# Quad_FC_V10_5.net
KiCad netlist of a schematic drawn in Altium Designer
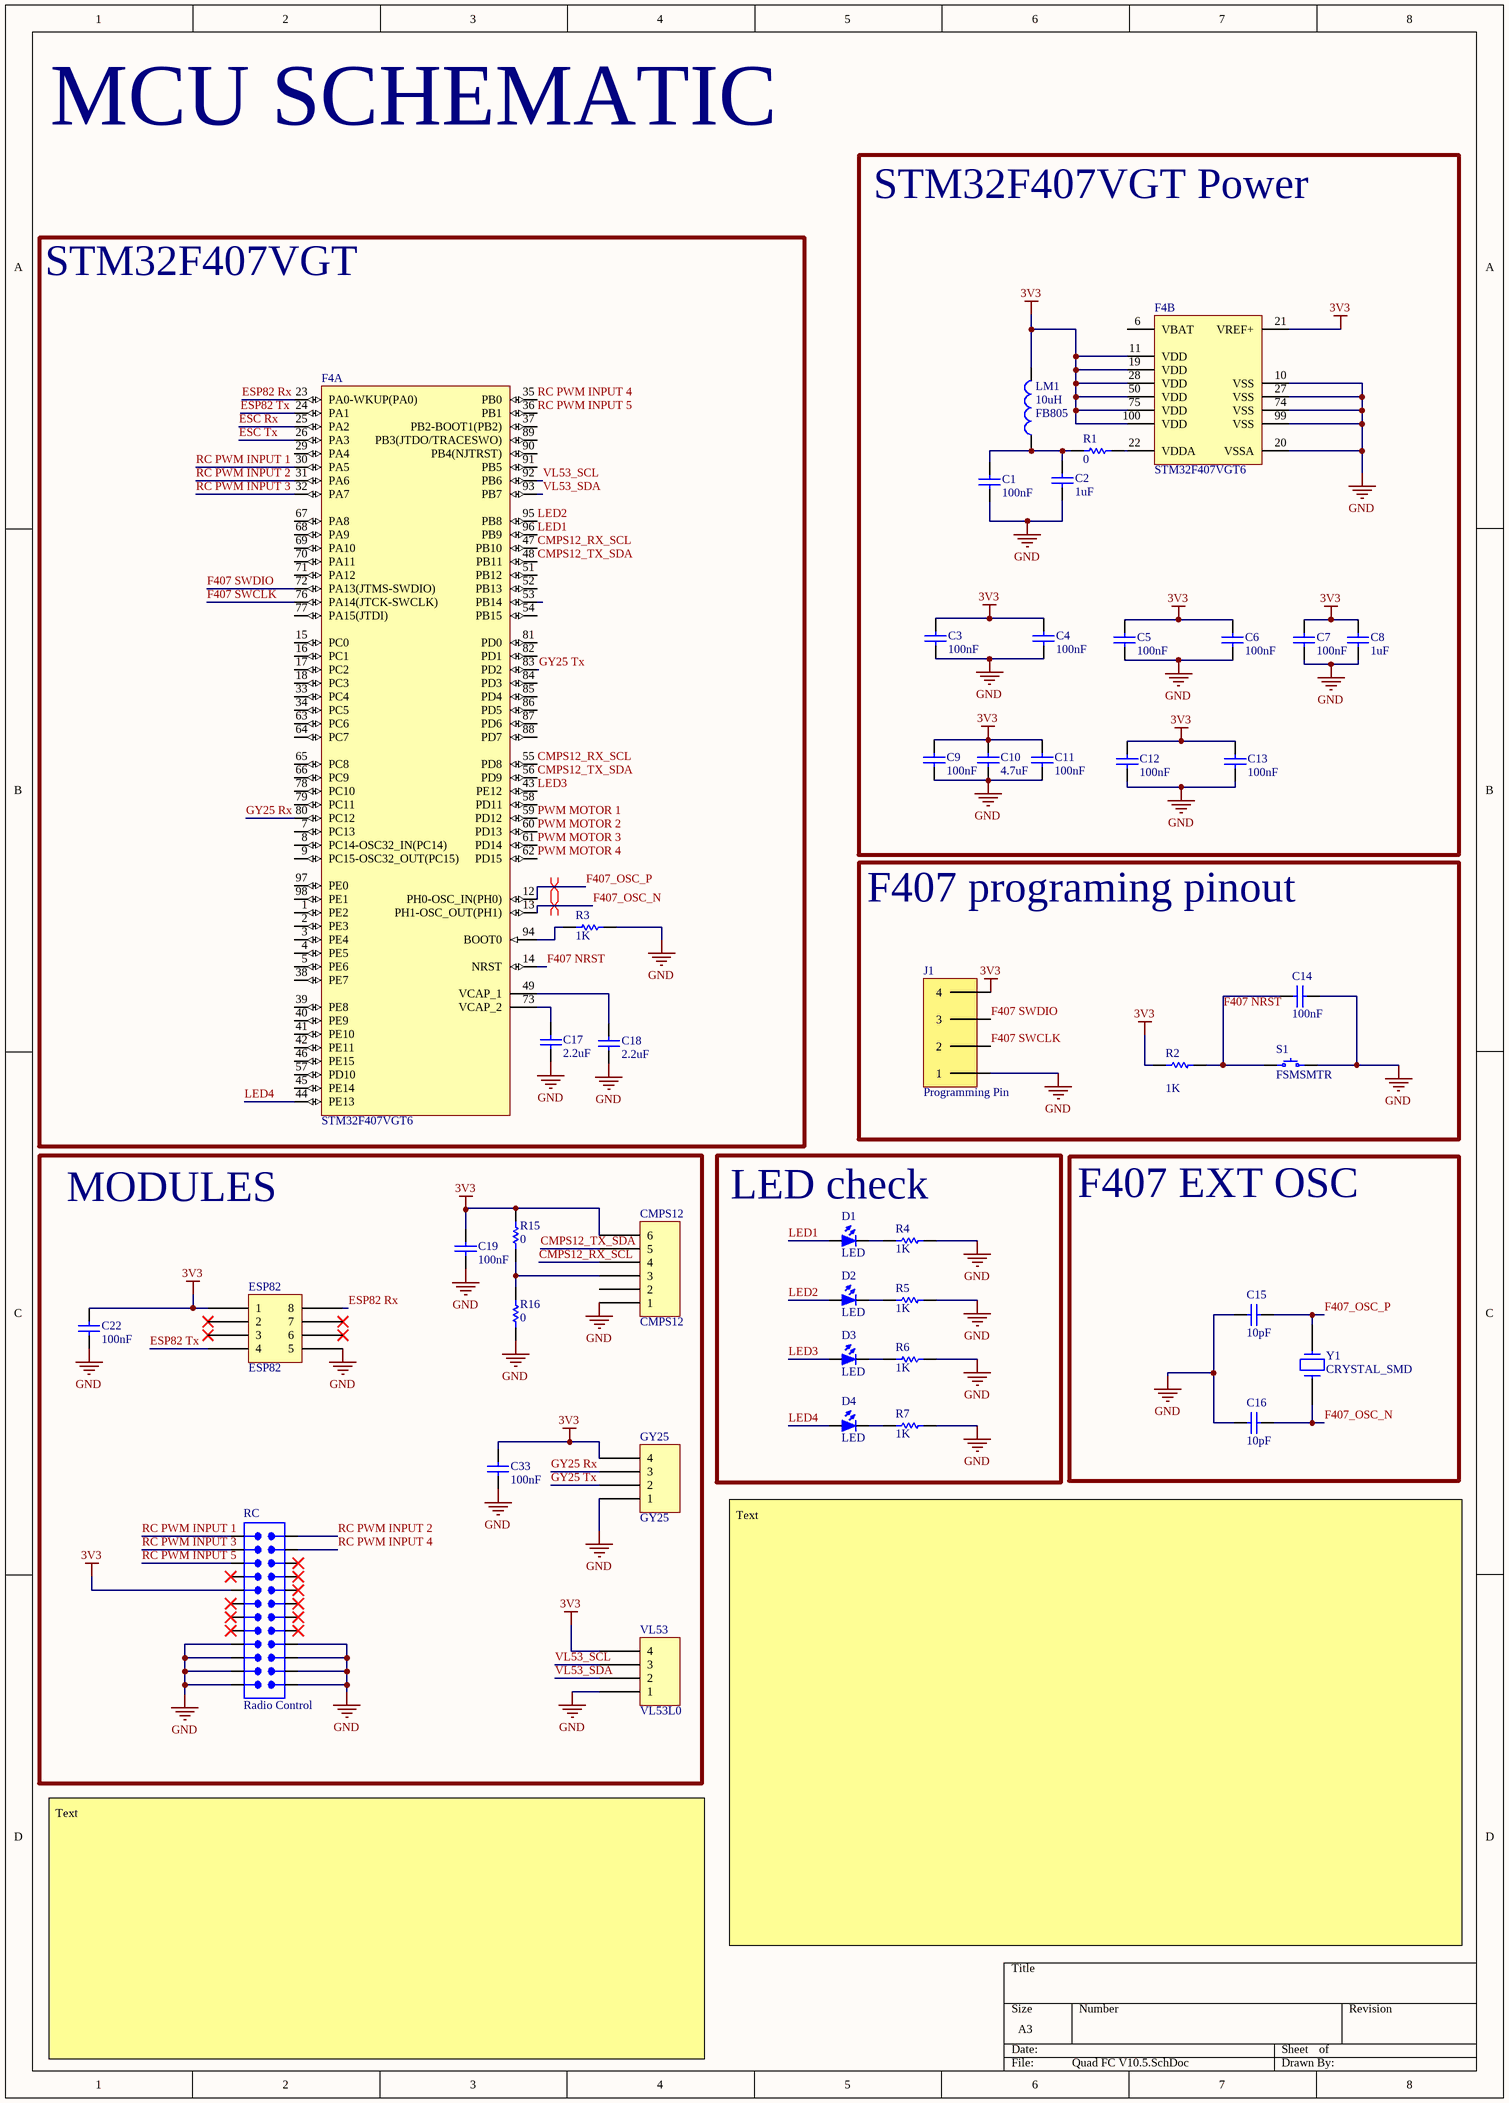
[diagram p0: Quad FC V10.5.SchDoc]

(export (version "E")
  (design (tool "Eeschema 10.0.6"))
  (components
    (comp (ref "C1")
      (value "100nF")
      (footprint "CAP0603")
      (description "F407VET6 Power CAP")
      (fields (field (name "DESIGNER") "Abbas Basereh"))
      (libsource (lib "2017AbbasBasereh9365731239 -ver1") (part "CAP SMD PACKAGE"))
    )
    (comp (ref "C2")
      (value "1uF")
      (footprint "CAP0603")
      (description "F407VET6 Power CAP")
      (fields (field (name "DESIGNER") "Abbas Basereh"))
      (libsource (lib "2017AbbasBasereh9365731239 -ver1") (part "CAP SMD PACKAGE"))
    )
    (comp (ref "C3")
      (value "100nF")
      (footprint "CAP0603")
      (description "F407VET6 Power CAP")
      (fields (field (name "DESIGNER") "Abbas Basereh"))
      (libsource (lib "2017AbbasBasereh9365731239 -ver1") (part "CAP SMD PACKAGE"))
    )
    (comp (ref "C4")
      (value "100nF")
      (footprint "CAP0603")
      (description "F407VET6 Power CAP")
      (fields (field (name "DESIGNER") "Abbas Basereh"))
      (libsource (lib "2017AbbasBasereh9365731239 -ver1") (part "CAP SMD PACKAGE"))
    )
    (comp (ref "C5")
      (value "100nF")
      (footprint "CAP0603")
      (description "F407VET6 Power CAP")
      (fields (field (name "DESIGNER") "Abbas Basereh"))
      (libsource (lib "2017AbbasBasereh9365731239 -ver1") (part "CAP SMD PACKAGE"))
    )
    (comp (ref "C6")
      (value "100nF")
      (footprint "CAP0603")
      (description "F407VET6 Power CAP")
      (fields (field (name "DESIGNER") "Abbas Basereh"))
      (libsource (lib "2017AbbasBasereh9365731239 -ver1") (part "CAP SMD PACKAGE"))
    )
    (comp (ref "C7")
      (value "100nF")
      (footprint "CAP0603")
      (description "F407VET6 Power CAP")
      (fields (field (name "DESIGNER") "Abbas Basereh"))
      (libsource (lib "2017AbbasBasereh9365731239 -ver1") (part "CAP SMD PACKAGE"))
    )
    (comp (ref "C8")
      (value "1uF")
      (footprint "CAP0603")
      (description "F407VET6 Power CAP")
      (fields (field (name "DESIGNER") "Abbas Basereh"))
      (libsource (lib "2017AbbasBasereh9365731239 -ver1") (part "CAP SMD PACKAGE"))
    )
    (comp (ref "C9")
      (value "100nF")
      (footprint "CAP0603")
      (description "F407VET6 Power CAP")
      (fields (field (name "DESIGNER") "Abbas Basereh"))
      (libsource (lib "2017AbbasBasereh9365731239 -ver1") (part "CAP SMD PACKAGE"))
    )
    (comp (ref "C10")
      (value "4.7uF")
      (footprint "CAP0603")
      (description "F407VET6 Power CAP")
      (fields (field (name "DESIGNER") "Abbas Basereh"))
      (libsource (lib "2017AbbasBasereh9365731239 -ver1") (part "CAP SMD PACKAGE"))
    )
    (comp (ref "C11")
      (value "100nF")
      (footprint "CAP0603")
      (description "F407VET6 Power CAP")
      (fields (field (name "DESIGNER") "Abbas Basereh"))
      (libsource (lib "2017AbbasBasereh9365731239 -ver1") (part "CAP SMD PACKAGE"))
    )
    (comp (ref "C12")
      (value "100nF")
      (footprint "CAP0603")
      (description "F407VET6 Power CAP")
      (fields (field (name "DESIGNER") "Abbas Basereh"))
      (libsource (lib "2017AbbasBasereh9365731239 -ver1") (part "CAP SMD PACKAGE"))
    )
    (comp (ref "C13")
      (value "100nF")
      (footprint "CAP0603")
      (description "F407VET6 Power CAP")
      (fields (field (name "DESIGNER") "Abbas Basereh"))
      (libsource (lib "2017AbbasBasereh9365731239 -ver1") (part "CAP SMD PACKAGE"))
    )
    (comp (ref "C14")
      (value "100nF")
      (footprint "CAP0603")
      (description "F407VET6 Power CAP")
      (fields (field (name "DESIGNER") "Abbas Basereh"))
      (libsource (lib "2017AbbasBasereh9365731239 -ver1") (part "CAP SMD PACKAGE"))
    )
    (comp (ref "C15")
      (value "10pF")
      (footprint "CAP0603")
      (description "F407VET6 Power CAP")
      (fields (field (name "DESIGNER") "Abbas Basereh"))
      (libsource (lib "2017AbbasBasereh9365731239 -ver1") (part "CAP SMD PACKAGE"))
    )
    (comp (ref "C16")
      (value "10pF")
      (footprint "CAP0603")
      (description "F407VET6 Power CAP")
      (fields (field (name "DESIGNER") "Abbas Basereh"))
      (libsource (lib "2017AbbasBasereh9365731239 -ver1") (part "CAP SMD PACKAGE"))
    )
    (comp (ref "C17")
      (value "2.2uF")
      (footprint "CAP0603")
      (description "F407VET6 Power CAP")
      (fields (field (name "DESIGNER") "Abbas Basereh"))
      (libsource (lib "2017AbbasBasereh9365731239 -ver1") (part "CAP SMD PACKAGE"))
    )
    (comp (ref "C18")
      (value "2.2uF")
      (footprint "CAP0603")
      (description "F407VET6 Power CAP")
      (fields (field (name "DESIGNER") "Abbas Basereh"))
      (libsource (lib "2017AbbasBasereh9365731239 -ver1") (part "CAP SMD PACKAGE"))
    )
    (comp (ref "C19")
      (value "100nF")
      (footprint "CAP0603")
      (description "F407VET6 Power CAP")
      (fields (field (name "DESIGNER") "Abbas Basereh"))
      (libsource (lib "2017AbbasBasereh9365731239 -ver1") (part "CAP SMD PACKAGE"))
    )
    (comp (ref "C22")
      (value "100nF")
      (footprint "CAP0603")
      (description "F407VET6 Power CAP")
      (fields (field (name "DESIGNER") "Abbas Basereh"))
      (libsource (lib "2017AbbasBasereh9365731239 -ver1") (part "CAP SMD PACKAGE"))
    )
    (comp (ref "C33")
      (value "100nF")
      (footprint "CAP0603")
      (description "F407VET6 Power CAP")
      (fields (field (name "DESIGNER") "Abbas Basereh"))
      (libsource (lib "2017AbbasBasereh9365731239 -ver1") (part "CAP SMD PACKAGE"))
    )
    (comp (ref "CMPS12")
      (value "CMPS12")
      (footprint "SAMTEC SSW-106-03-T-S")
      (description "CONN RCPT 6POS 0.1 TIN PCB")
      (fields (field (name "PART NUMBER") "SSW-106-03-T-S") (field (name "MANUFACTURER") "Samtec Inc."))
      (libsource (lib "Celestial Altium Library - altium_library (1)") (part "6 Pin"))
    )
    (comp (ref "D1")
      (value "LED")
      (footprint "0603 - LED")
      (description "Led")
      (fields (field (name "PUBLISHER") "Altium Limited"))
      (libsource (lib "Sajad_Altium_Library") (part "LED"))
    )
    (comp (ref "D2")
      (value "LED")
      (footprint "0603 - LED")
      (description "Led")
      (fields (field (name "PUBLISHER") "Altium Limited"))
      (libsource (lib "Sajad_Altium_Library") (part "LED"))
    )
    (comp (ref "D3")
      (value "LED")
      (footprint "0603 - LED")
      (description "Led")
      (fields (field (name "PUBLISHER") "Altium Limited"))
      (libsource (lib "Sajad_Altium_Library") (part "LED"))
    )
    (comp (ref "D4")
      (value "LED")
      (footprint "0603 - LED")
      (description "Led")
      (fields (field (name "PUBLISHER") "Altium Limited"))
      (libsource (lib "Sajad_Altium_Library") (part "LED"))
    )
    (comp (ref "ESP82")
      (value "ESP82")
      (footprint "HARWIN M20-7830445")
      (description "CONN RCPT 8POS 0.1 GOLD PCB")
      (fields (field (name "PART NUMBER") "M20-7830442") (field (name "MANUFACTURER") "Harwin Inc."))
      (libsource (lib "Celestial Altium Library - altium_library (1)") (part "2X4 PIN DU"))
    )
    (comp (ref "F4")
      (value "STM32F407VGT6")
      (footprint "STM-LQFP100_N")
      (fields (field (name "MANUFACTURER") "STMicroelectronics"))
      (libsource (lib "STMicroelectronics STM32 F4") (part "STM32F407VGT6"))
    )
    (comp (ref "GY25")
      (value "GY25")
      (footprint "SAMTEC SSW-104-03-T-S")
      (description "CONN RCPT 4POS 0.1 TIN PCB")
      (fields (field (name "PART NUMBER") "SSW-104-03-T-S") (field (name "MANUFACTURER") "Samtec Inc."))
      (libsource (lib "Celestial Altium Library - altium_library (1)") (part "4 Pin"))
    )
    (comp (ref "J1")
      (value "Programming Pin")
      (footprint "HEADER 4X1")
      (libsource (lib "AltiumLib1") (part "Header4X1"))
    )
    (comp (ref "LM1")
      (value "10uH")
      (footprint "0805L")
      (description "Inductor")
      (fields (field (name "ALTIUM_VALUE") "FB805") (field (name "PUBLISHER") "Altium Limited"))
      (libsource (lib "2017AbbasBasereh9365731239 -ver1") (part "L SMA 0.25W"))
    )
    (comp (ref "R1")
      (value "0")
      (footprint "RES0603")
      (description "TOTAL SMD RESISTOR PACK")
      (fields (field (name "DESIGNER") "Abbas Basereh"))
      (libsource (lib "2017AbbasBasereh9365731239 -ver1") (part "RES SMD PACKAGE"))
    )
    (comp (ref "R2")
      (value "1K")
      (footprint "RES0603")
      (description "TOTAL SMD RESISTOR PACK")
      (fields (field (name "DESIGNER") "Abbas Basereh"))
      (libsource (lib "2017AbbasBasereh9365731239 -ver1") (part "RES SMD PACKAGE"))
    )
    (comp (ref "R3")
      (value "1K")
      (footprint "RES0603")
      (description "TOTAL SMD RESISTOR PACK")
      (fields (field (name "DESIGNER") "Abbas Basereh"))
      (libsource (lib "2017AbbasBasereh9365731239 -ver1") (part "RES SMD PACKAGE"))
    )
    (comp (ref "R4")
      (value "1K")
      (footprint "RES0603")
      (description "TOTAL SMD RESISTOR PACK")
      (fields (field (name "DESIGNER") "Abbas Basereh"))
      (libsource (lib "2017AbbasBasereh9365731239 -ver1") (part "RES SMD PACKAGE"))
    )
    (comp (ref "R5")
      (value "1K")
      (footprint "RES0603")
      (description "TOTAL SMD RESISTOR PACK")
      (fields (field (name "DESIGNER") "Abbas Basereh"))
      (libsource (lib "2017AbbasBasereh9365731239 -ver1") (part "RES SMD PACKAGE"))
    )
    (comp (ref "R6")
      (value "1K")
      (footprint "RES0603")
      (description "TOTAL SMD RESISTOR PACK")
      (fields (field (name "DESIGNER") "Abbas Basereh"))
      (libsource (lib "2017AbbasBasereh9365731239 -ver1") (part "RES SMD PACKAGE"))
    )
    (comp (ref "R7")
      (value "1K")
      (footprint "RES0603")
      (description "TOTAL SMD RESISTOR PACK")
      (fields (field (name "DESIGNER") "Abbas Basereh"))
      (libsource (lib "2017AbbasBasereh9365731239 -ver1") (part "RES SMD PACKAGE"))
    )
    (comp (ref "R15")
      (value "0")
      (footprint "RES0603")
      (description "TOTAL SMD RESISTOR PACK")
      (fields (field (name "DESIGNER") "Abbas Basereh"))
      (libsource (lib "2017AbbasBasereh9365731239 -ver1") (part "RES SMD PACKAGE"))
    )
    (comp (ref "R16")
      (value "0")
      (footprint "RES0603")
      (description "TOTAL SMD RESISTOR PACK")
      (fields (field (name "DESIGNER") "Abbas Basereh"))
      (libsource (lib "2017AbbasBasereh9365731239 -ver1") (part "RES SMD PACKAGE"))
    )
    (comp (ref "RC")
      (value "Radio Control")
      (footprint "HEADER8X3:HEADER8X3")
      (description "Male Header 2X12")
      (libsource (lib "SJ Sockets & Connectors") (part "MHDR_2X12"))
    )
    (comp (ref "S1")
      (value "FSMSMTR")
      (footprint "TE FSMSMTR")
      (description "SWITCH TACTILE SPST-NO 0.05A 24V")
      (fields (field (name "MANUFACTURER") "TE Connectivity ALCOSWITCH Switches"))
      (libsource (lib "Celestial Altium Library - altium_library (1)") (part "SPST-NO 2 PIN"))
    )
    (comp (ref "VL53")
      (value "VL53L0")
      (footprint "JST SM04B-SURS-TF")
      (description "CONN HEADER SMD R/A 4POS 0.8MM")
      (fields (field (name "PART NUMBER") "SM04B-SURS-TF(LF)(SN)"))
      (libsource (lib "Celestial Altium Library - altium_library (1)") (part "4 Pin"))
    )
    (comp (ref "Y1")
      (value "CRYSTAL_SMD")
      (footprint "My_Crystal - SMD")
      (description "Crystal")
      (libsource (lib "AMINLIB") (part "CRYSTAL_SMD"))
    )
  )
  (nets
    (net (code "1") (name "/CMPS12_RX_SCL") (class "Default")
      (node (ref "CMPS12") (pin "4") (pinfunction "4_4") (pintype "passive"))
      (node (ref "F4") (pin "47") (pinfunction "PB10_47") (pintype "bidirectional"))
      (node (ref "F4") (pin "55") (pinfunction "PD8_55") (pintype "bidirectional"))
    )
    (net (code "2") (name "/CMPS12_TX_SDA") (class "Default")
      (node (ref "CMPS12") (pin "5") (pinfunction "5_5") (pintype "passive"))
      (node (ref "F4") (pin "48") (pinfunction "PB11_48") (pintype "bidirectional"))
      (node (ref "F4") (pin "56") (pinfunction "PD9_56") (pintype "bidirectional"))
    )
    (net (code "3") (name "/ESC Rx") (class "Default")
      (node (ref "F4") (pin "25") (pinfunction "PA2_25") (pintype "bidirectional"))
    )
    (net (code "4") (name "/ESC Tx") (class "Default")
      (node (ref "F4") (pin "26") (pinfunction "PA3_26") (pintype "bidirectional"))
    )
    (net (code "5") (name "/ESP82 Rx") (class "Default")
      (node (ref "ESP82") (pin "8") (pinfunction "8_8") (pintype "passive"))
      (node (ref "F4") (pin "23") (pinfunction "PA0-WKUP(PA0)_23") (pintype "bidirectional"))
    )
    (net (code "6") (name "/ESP82 Tx") (class "Default")
      (node (ref "ESP82") (pin "4") (pinfunction "4_4") (pintype "passive"))
      (node (ref "F4") (pin "24") (pinfunction "PA1_24") (pintype "bidirectional"))
    )
    (net (code "7") (name "/F407 NRST") (class "Default")
      (node (ref "C14") (pin "1") (pinfunction "1_1") (pintype "passive"))
      (node (ref "F4") (pin "14") (pinfunction "NRST_14") (pintype "bidirectional"))
      (node (ref "R2") (pin "2") (pinfunction "2_2") (pintype "passive"))
      (node (ref "S1") (pin "1") (pinfunction "1_1") (pintype "passive"))
    )
    (net (code "8") (name "/F407 SWCLK") (class "Default")
      (node (ref "F4") (pin "76") (pinfunction "PA14(JTCK-SWCLK)_76") (pintype "bidirectional"))
      (node (ref "J1") (pin "2") (pinfunction "2_2") (pintype "passive"))
    )
    (net (code "9") (name "/F407 SWDIO") (class "Default")
      (node (ref "F4") (pin "72") (pinfunction "PA13(JTMS-SWDIO)_72") (pintype "bidirectional"))
      (node (ref "J1") (pin "3") (pinfunction "3_3") (pintype "passive"))
    )
    (net (code "10") (name "/F407_OSC_N") (class "Default")
      (node (ref "C16") (pin "1") (pinfunction "1_1") (pintype "passive"))
      (node (ref "F4") (pin "13") (pinfunction "PH1-OSC_OUT(PH1)_13") (pintype "bidirectional"))
      (node (ref "Y1") (pin "1") (pinfunction "1_1") (pintype "passive"))
    )
    (net (code "11") (name "/F407_OSC_P") (class "Default")
      (node (ref "C15") (pin "2") (pinfunction "2_2") (pintype "passive"))
      (node (ref "F4") (pin "12") (pinfunction "PH0-OSC_IN(PH0)_12") (pintype "bidirectional"))
      (node (ref "Y1") (pin "2") (pinfunction "2_2") (pintype "passive"))
    )
    (net (code "12") (name "/GY25 Rx") (class "Default")
      (node (ref "F4") (pin "80") (pinfunction "PC12_80") (pintype "bidirectional"))
      (node (ref "GY25") (pin "3") (pinfunction "3_3") (pintype "passive"))
    )
    (net (code "13") (name "/GY25 Tx") (class "Default")
      (node (ref "F4") (pin "83") (pinfunction "PD2_83") (pintype "bidirectional"))
      (node (ref "GY25") (pin "2") (pinfunction "2_2") (pintype "passive"))
    )
    (net (code "14") (name "/LED1") (class "Default")
      (node (ref "D1") (pin "1") (pinfunction "A_1") (pintype "passive"))
      (node (ref "F4") (pin "96") (pinfunction "PB9_96") (pintype "bidirectional"))
    )
    (net (code "15") (name "/LED2") (class "Default")
      (node (ref "D2") (pin "1") (pinfunction "A_1") (pintype "passive"))
      (node (ref "F4") (pin "95") (pinfunction "PB8_95") (pintype "bidirectional"))
    )
    (net (code "16") (name "/LED3") (class "Default")
      (node (ref "D3") (pin "1") (pinfunction "A_1") (pintype "passive"))
      (node (ref "F4") (pin "43") (pinfunction "PE12_43") (pintype "bidirectional"))
    )
    (net (code "17") (name "/LED4") (class "Default")
      (node (ref "D4") (pin "1") (pinfunction "A_1") (pintype "passive"))
      (node (ref "F4") (pin "44") (pinfunction "PE13_44") (pintype "bidirectional"))
    )
    (net (code "18") (name "/PWM MOTOR 1") (class "Default")
      (node (ref "F4") (pin "59") (pinfunction "PD12_59") (pintype "bidirectional"))
    )
    (net (code "19") (name "/PWM MOTOR 2") (class "Default")
      (node (ref "F4") (pin "60") (pinfunction "PD13_60") (pintype "bidirectional"))
    )
    (net (code "20") (name "/PWM MOTOR 3") (class "Default")
      (node (ref "F4") (pin "61") (pinfunction "PD14_61") (pintype "bidirectional"))
    )
    (net (code "21") (name "/PWM MOTOR 4") (class "Default")
      (node (ref "F4") (pin "62") (pinfunction "PD15_62") (pintype "bidirectional"))
    )
    (net (code "22") (name "/RC PWM INPUT 1") (class "Default")
      (node (ref "F4") (pin "30") (pinfunction "PA5_30") (pintype "bidirectional"))
      (node (ref "RC") (pin "1") (pinfunction "1_1") (pintype "passive"))
    )
    (net (code "23") (name "/RC PWM INPUT 2") (class "Default")
      (node (ref "F4") (pin "31") (pinfunction "PA6_31") (pintype "bidirectional"))
      (node (ref "RC") (pin "2") (pinfunction "2_2") (pintype "passive"))
    )
    (net (code "24") (name "/RC PWM INPUT 3") (class "Default")
      (node (ref "F4") (pin "32") (pinfunction "PA7_32") (pintype "bidirectional"))
      (node (ref "RC") (pin "3") (pinfunction "3_3") (pintype "passive"))
    )
    (net (code "25") (name "/RC PWM INPUT 4") (class "Default")
      (node (ref "F4") (pin "35") (pinfunction "PB0_35") (pintype "bidirectional"))
      (node (ref "RC") (pin "4") (pinfunction "4_4") (pintype "passive"))
    )
    (net (code "26") (name "/RC PWM INPUT 5") (class "Default")
      (node (ref "F4") (pin "36") (pinfunction "PB1_36") (pintype "bidirectional"))
      (node (ref "RC") (pin "5") (pinfunction "5_5") (pintype "passive"))
    )
    (net (code "27") (name "/VL53_SCL") (class "Default")
      (node (ref "F4") (pin "92") (pinfunction "PB6_92") (pintype "bidirectional"))
      (node (ref "VL53") (pin "3") (pinfunction "3_3") (pintype "passive"))
    )
    (net (code "28") (name "/VL53_SDA") (class "Default")
      (node (ref "F4") (pin "93") (pinfunction "PB7_93") (pintype "bidirectional"))
      (node (ref "VL53") (pin "2") (pinfunction "2_2") (pintype "passive"))
    )
    (net (code "29") (name "3V3") (class "Default")
      (node (ref "C10") (pin "2") (pinfunction "2_2") (pintype "passive"))
      (node (ref "C11") (pin "2") (pinfunction "2_2") (pintype "passive"))
      (node (ref "C12") (pin "2") (pinfunction "2_2") (pintype "passive"))
      (node (ref "C13") (pin "2") (pinfunction "2_2") (pintype "passive"))
      (node (ref "C19") (pin "1") (pinfunction "1_1") (pintype "passive"))
      (node (ref "C22") (pin "1") (pinfunction "1_1") (pintype "passive"))
      (node (ref "C3") (pin "2") (pinfunction "2_2") (pintype "passive"))
      (node (ref "C33") (pin "1") (pinfunction "1_1") (pintype "passive"))
      (node (ref "C4") (pin "2") (pinfunction "2_2") (pintype "passive"))
      (node (ref "C5") (pin "2") (pinfunction "2_2") (pintype "passive"))
      (node (ref "C6") (pin "2") (pinfunction "2_2") (pintype "passive"))
      (node (ref "C7") (pin "1") (pinfunction "1_1") (pintype "passive"))
      (node (ref "C8") (pin "1") (pinfunction "1_1") (pintype "passive"))
      (node (ref "C9") (pin "2") (pinfunction "2_2") (pintype "passive"))
      (node (ref "CMPS12") (pin "6") (pinfunction "6_6") (pintype "passive"))
      (node (ref "ESP82") (pin "1") (pinfunction "1_1") (pintype "passive"))
      (node (ref "F4") (pin "100") (pinfunction "VDD_100") (pintype "power_in"))
      (node (ref "F4") (pin "11") (pinfunction "VDD_11") (pintype "power_in"))
      (node (ref "F4") (pin "19") (pinfunction "VDD_19") (pintype "power_in"))
      (node (ref "F4") (pin "21") (pinfunction "VREF+_21") (pintype "power_in"))
      (node (ref "F4") (pin "28") (pinfunction "VDD_28") (pintype "power_in"))
      (node (ref "F4") (pin "50") (pinfunction "VDD_50") (pintype "power_in"))
      (node (ref "F4") (pin "75") (pinfunction "VDD_75") (pintype "power_in"))
      (node (ref "GY25") (pin "4") (pinfunction "4_4") (pintype "passive"))
      (node (ref "J1") (pin "4") (pinfunction "4_4") (pintype "passive"))
      (node (ref "LM1") (pin "2") (pinfunction "2_2") (pintype "passive"))
      (node (ref "R15") (pin "2") (pinfunction "2_2") (pintype "passive"))
      (node (ref "R2") (pin "1") (pinfunction "1_1") (pintype "passive"))
      (node (ref "RC") (pin "9") (pinfunction "9_9") (pintype "passive"))
      (node (ref "VL53") (pin "4") (pinfunction "4_4") (pintype "passive"))
    )
    (net (code "30") (name "GND") (class "Default")
      (node (ref "C1") (pin "1") (pinfunction "1_1") (pintype "passive"))
      (node (ref "C10") (pin "1") (pinfunction "1_1") (pintype "passive"))
      (node (ref "C11") (pin "1") (pinfunction "1_1") (pintype "passive"))
      (node (ref "C12") (pin "1") (pinfunction "1_1") (pintype "passive"))
      (node (ref "C13") (pin "1") (pinfunction "1_1") (pintype "passive"))
      (node (ref "C14") (pin "2") (pinfunction "2_2") (pintype "passive"))
      (node (ref "C15") (pin "1") (pinfunction "1_1") (pintype "passive"))
      (node (ref "C16") (pin "2") (pinfunction "2_2") (pintype "passive"))
      (node (ref "C17") (pin "2") (pinfunction "2_2") (pintype "passive"))
      (node (ref "C18") (pin "2") (pinfunction "2_2") (pintype "passive"))
      (node (ref "C19") (pin "2") (pinfunction "2_2") (pintype "passive"))
      (node (ref "C2") (pin "1") (pinfunction "1_1") (pintype "passive"))
      (node (ref "C22") (pin "2") (pinfunction "2_2") (pintype "passive"))
      (node (ref "C3") (pin "1") (pinfunction "1_1") (pintype "passive"))
      (node (ref "C33") (pin "2") (pinfunction "2_2") (pintype "passive"))
      (node (ref "C4") (pin "1") (pinfunction "1_1") (pintype "passive"))
      (node (ref "C5") (pin "1") (pinfunction "1_1") (pintype "passive"))
      (node (ref "C6") (pin "1") (pinfunction "1_1") (pintype "passive"))
      (node (ref "C7") (pin "2") (pinfunction "2_2") (pintype "passive"))
      (node (ref "C8") (pin "2") (pinfunction "2_2") (pintype "passive"))
      (node (ref "C9") (pin "1") (pinfunction "1_1") (pintype "passive"))
      (node (ref "CMPS12") (pin "1") (pinfunction "1_1") (pintype "passive"))
      (node (ref "ESP82") (pin "5") (pinfunction "5_5") (pintype "passive"))
      (node (ref "F4") (pin "10") (pinfunction "VSS_10") (pintype "power_in"))
      (node (ref "F4") (pin "20") (pinfunction "VSSA_20") (pintype "power_in"))
      (node (ref "F4") (pin "27") (pinfunction "VSS_27") (pintype "power_in"))
      (node (ref "F4") (pin "74") (pinfunction "VSS_74") (pintype "power_in"))
      (node (ref "F4") (pin "99") (pinfunction "VSS_99") (pintype "power_in"))
      (node (ref "GY25") (pin "1") (pinfunction "1_1") (pintype "passive"))
      (node (ref "J1") (pin "1") (pinfunction "1_1") (pintype "passive"))
      (node (ref "R16") (pin "1") (pinfunction "1_1") (pintype "passive"))
      (node (ref "R3") (pin "2") (pinfunction "2_2") (pintype "passive"))
      (node (ref "R4") (pin "2") (pinfunction "2_2") (pintype "passive"))
      (node (ref "R5") (pin "2") (pinfunction "2_2") (pintype "passive"))
      (node (ref "R6") (pin "2") (pinfunction "2_2") (pintype "passive"))
      (node (ref "R7") (pin "2") (pinfunction "2_2") (pintype "passive"))
      (node (ref "RC") (pin "17") (pinfunction "17_17") (pintype "passive"))
      (node (ref "RC") (pin "18") (pinfunction "18_18") (pintype "passive"))
      (node (ref "RC") (pin "19") (pinfunction "19_19") (pintype "passive"))
      (node (ref "RC") (pin "20") (pinfunction "20_20") (pintype "passive"))
      (node (ref "RC") (pin "21") (pinfunction "21_21") (pintype "passive"))
      (node (ref "RC") (pin "22") (pinfunction "22_22") (pintype "passive"))
      (node (ref "RC") (pin "23") (pinfunction "23_23") (pintype "passive"))
      (node (ref "RC") (pin "24") (pinfunction "24_24") (pintype "passive"))
      (node (ref "S1") (pin "2") (pinfunction "2_2") (pintype "passive"))
      (node (ref "VL53") (pin "1") (pinfunction "1_1") (pintype "passive"))
    )
    (net (code "31") (name "Net-(C1-Pad2)") (class "Default")
      (node (ref "C1") (pin "2") (pinfunction "2_2") (pintype "passive"))
      (node (ref "C2") (pin "2") (pinfunction "2_2") (pintype "passive"))
      (node (ref "LM1") (pin "1") (pinfunction "1_1") (pintype "passive"))
      (node (ref "R1") (pin "1") (pinfunction "1_1") (pintype "passive"))
    )
    (net (code "32") (name "Net-(CMPS12-Pad3)") (class "Default")
      (node (ref "CMPS12") (pin "3") (pinfunction "3_3") (pintype "passive"))
      (node (ref "R15") (pin "1") (pinfunction "1_1") (pintype "passive"))
      (node (ref "R16") (pin "2") (pinfunction "2_2") (pintype "passive"))
    )
    (net (code "33") (name "Net-(D1-K)") (class "Default")
      (node (ref "D1") (pin "2") (pinfunction "K_2") (pintype "passive"))
      (node (ref "R4") (pin "1") (pinfunction "1_1") (pintype "passive"))
    )
    (net (code "34") (name "Net-(D2-K)") (class "Default")
      (node (ref "D2") (pin "2") (pinfunction "K_2") (pintype "passive"))
      (node (ref "R5") (pin "1") (pinfunction "1_1") (pintype "passive"))
    )
    (net (code "35") (name "Net-(D3-K)") (class "Default")
      (node (ref "D3") (pin "2") (pinfunction "K_2") (pintype "passive"))
      (node (ref "R6") (pin "1") (pinfunction "1_1") (pintype "passive"))
    )
    (net (code "36") (name "Net-(D4-K)") (class "Default")
      (node (ref "D4") (pin "2") (pinfunction "K_2") (pintype "passive"))
      (node (ref "R7") (pin "1") (pinfunction "1_1") (pintype "passive"))
    )
    (net (code "37") (name "Net-(F4A-BOOT0)") (class "Default")
      (node (ref "F4") (pin "94") (pinfunction "BOOT0_94") (pintype "input"))
      (node (ref "R3") (pin "1") (pinfunction "1_1") (pintype "passive"))
    )
    (net (code "38") (name "Net-(F4A-VCAP_1)") (class "Default")
      (node (ref "C18") (pin "1") (pinfunction "1_1") (pintype "passive"))
      (node (ref "F4") (pin "49") (pinfunction "VCAP_1_49") (pintype "power_in"))
    )
    (net (code "39") (name "Net-(F4A-VCAP_2)") (class "Default")
      (node (ref "C17") (pin "1") (pinfunction "1_1") (pintype "passive"))
      (node (ref "F4") (pin "73") (pinfunction "VCAP_2_73") (pintype "power_in"))
    )
    (net (code "40") (name "Net-(F4B-VDDA)") (class "Default")
      (node (ref "F4") (pin "22") (pinfunction "VDDA_22") (pintype "power_in"))
      (node (ref "R1") (pin "2") (pinfunction "2_2") (pintype "passive"))
    )
    (net (code "41") (name "unconnected-(CMPS12-Pad2)") (class "Default")
      (node (ref "CMPS12") (pin "2") (pinfunction "2_2") (pintype "passive"))
    )
    (net (code "42") (name "unconnected-(ESP82-Pad2)") (class "Default")
      (node (ref "ESP82") (pin "2") (pinfunction "2_2") (pintype "passive+no_connect"))
    )
    (net (code "43") (name "unconnected-(ESP82-Pad3)") (class "Default")
      (node (ref "ESP82") (pin "3") (pinfunction "3_3") (pintype "passive+no_connect"))
    )
    (net (code "44") (name "unconnected-(ESP82-Pad6)") (class "Default")
      (node (ref "ESP82") (pin "6") (pinfunction "6_6") (pintype "passive+no_connect"))
    )
    (net (code "45") (name "unconnected-(ESP82-Pad7)") (class "Default")
      (node (ref "ESP82") (pin "7") (pinfunction "7_7") (pintype "passive+no_connect"))
    )
    (net (code "46") (name "unconnected-(F4A-PA4-Pad29)") (class "Default")
      (node (ref "F4") (pin "29") (pinfunction "PA4_29") (pintype "bidirectional"))
    )
    (net (code "47") (name "unconnected-(F4A-PA8-Pad67)") (class "Default")
      (node (ref "F4") (pin "67") (pinfunction "PA8_67") (pintype "bidirectional"))
    )
    (net (code "48") (name "unconnected-(F4A-PA9-Pad68)") (class "Default")
      (node (ref "F4") (pin "68") (pinfunction "PA9_68") (pintype "bidirectional"))
    )
    (net (code "49") (name "unconnected-(F4A-PA10-Pad69)") (class "Default")
      (node (ref "F4") (pin "69") (pinfunction "PA10_69") (pintype "bidirectional"))
    )
    (net (code "50") (name "unconnected-(F4A-PA11-Pad70)") (class "Default")
      (node (ref "F4") (pin "70") (pinfunction "PA11_70") (pintype "bidirectional"))
    )
    (net (code "51") (name "unconnected-(F4A-PA12-Pad71)") (class "Default")
      (node (ref "F4") (pin "71") (pinfunction "PA12_71") (pintype "bidirectional"))
    )
    (net (code "52") (name "unconnected-(F4A-PA15(JTDI)-Pad77)") (class "Default")
      (node (ref "F4") (pin "77") (pinfunction "PA15(JTDI)_77") (pintype "bidirectional"))
    )
    (net (code "53") (name "unconnected-(F4A-PB2-BOOT1(PB2)-Pad37)") (class "Default")
      (node (ref "F4") (pin "37") (pinfunction "PB2-BOOT1(PB2)_37") (pintype "bidirectional"))
    )
    (net (code "54") (name "unconnected-(F4A-PB3(JTDO{slash}TRACESWO)-Pad89)") (class "Default")
      (node (ref "F4") (pin "89") (pinfunction "PB3(JTDO/TRACESWO)_89") (pintype "bidirectional"))
    )
    (net (code "55") (name "unconnected-(F4A-PB4(NJTRST)-Pad90)") (class "Default")
      (node (ref "F4") (pin "90") (pinfunction "PB4(NJTRST)_90") (pintype "bidirectional"))
    )
    (net (code "56") (name "unconnected-(F4A-PB5-Pad91)") (class "Default")
      (node (ref "F4") (pin "91") (pinfunction "PB5_91") (pintype "bidirectional"))
    )
    (net (code "57") (name "unconnected-(F4A-PB12-Pad51)") (class "Default")
      (node (ref "F4") (pin "51") (pinfunction "PB12_51") (pintype "bidirectional"))
    )
    (net (code "58") (name "unconnected-(F4A-PB13-Pad52)") (class "Default")
      (node (ref "F4") (pin "52") (pinfunction "PB13_52") (pintype "bidirectional"))
    )
    (net (code "59") (name "unconnected-(F4A-PB14-Pad53)") (class "Default")
      (node (ref "F4") (pin "53") (pinfunction "PB14_53") (pintype "bidirectional"))
    )
    (net (code "60") (name "unconnected-(F4A-PB15-Pad54)") (class "Default")
      (node (ref "F4") (pin "54") (pinfunction "PB15_54") (pintype "bidirectional"))
    )
    (net (code "61") (name "unconnected-(F4A-PC0-Pad15)") (class "Default")
      (node (ref "F4") (pin "15") (pinfunction "PC0_15") (pintype "bidirectional"))
    )
    (net (code "62") (name "unconnected-(F4A-PC1-Pad16)") (class "Default")
      (node (ref "F4") (pin "16") (pinfunction "PC1_16") (pintype "bidirectional"))
    )
    (net (code "63") (name "unconnected-(F4A-PC2-Pad17)") (class "Default")
      (node (ref "F4") (pin "17") (pinfunction "PC2_17") (pintype "bidirectional"))
    )
    (net (code "64") (name "unconnected-(F4A-PC3-Pad18)") (class "Default")
      (node (ref "F4") (pin "18") (pinfunction "PC3_18") (pintype "bidirectional"))
    )
    (net (code "65") (name "unconnected-(F4A-PC4-Pad33)") (class "Default")
      (node (ref "F4") (pin "33") (pinfunction "PC4_33") (pintype "bidirectional"))
    )
    (net (code "66") (name "unconnected-(F4A-PC5-Pad34)") (class "Default")
      (node (ref "F4") (pin "34") (pinfunction "PC5_34") (pintype "bidirectional"))
    )
    (net (code "67") (name "unconnected-(F4A-PC6-Pad63)") (class "Default")
      (node (ref "F4") (pin "63") (pinfunction "PC6_63") (pintype "bidirectional"))
    )
    (net (code "68") (name "unconnected-(F4A-PC7-Pad64)") (class "Default")
      (node (ref "F4") (pin "64") (pinfunction "PC7_64") (pintype "bidirectional"))
    )
    (net (code "69") (name "unconnected-(F4A-PC8-Pad65)") (class "Default")
      (node (ref "F4") (pin "65") (pinfunction "PC8_65") (pintype "bidirectional"))
    )
    (net (code "70") (name "unconnected-(F4A-PC9-Pad66)") (class "Default")
      (node (ref "F4") (pin "66") (pinfunction "PC9_66") (pintype "bidirectional"))
    )
    (net (code "71") (name "unconnected-(F4A-PC10-Pad78)") (class "Default")
      (node (ref "F4") (pin "78") (pinfunction "PC10_78") (pintype "bidirectional"))
    )
    (net (code "72") (name "unconnected-(F4A-PC11-Pad79)") (class "Default")
      (node (ref "F4") (pin "79") (pinfunction "PC11_79") (pintype "bidirectional"))
    )
    (net (code "73") (name "unconnected-(F4A-PC13-Pad7)") (class "Default")
      (node (ref "F4") (pin "7") (pinfunction "PC13_7") (pintype "bidirectional"))
    )
    (net (code "74") (name "unconnected-(F4A-PC14-OSC32_IN(PC14)-Pad8)") (class "Default")
      (node (ref "F4") (pin "8") (pinfunction "PC14-OSC32_IN(PC14)_8") (pintype "bidirectional"))
    )
    (net (code "75") (name "unconnected-(F4A-PC15-OSC32_OUT(PC15)-Pad9)") (class "Default")
      (node (ref "F4") (pin "9") (pinfunction "PC15-OSC32_OUT(PC15)_9") (pintype "bidirectional"))
    )
    (net (code "76") (name "unconnected-(F4A-PD0-Pad81)") (class "Default")
      (node (ref "F4") (pin "81") (pinfunction "PD0_81") (pintype "bidirectional"))
    )
    (net (code "77") (name "unconnected-(F4A-PD1-Pad82)") (class "Default")
      (node (ref "F4") (pin "82") (pinfunction "PD1_82") (pintype "bidirectional"))
    )
    (net (code "78") (name "unconnected-(F4A-PD3-Pad84)") (class "Default")
      (node (ref "F4") (pin "84") (pinfunction "PD3_84") (pintype "bidirectional"))
    )
    (net (code "79") (name "unconnected-(F4A-PD4-Pad85)") (class "Default")
      (node (ref "F4") (pin "85") (pinfunction "PD4_85") (pintype "bidirectional"))
    )
    (net (code "80") (name "unconnected-(F4A-PD5-Pad86)") (class "Default")
      (node (ref "F4") (pin "86") (pinfunction "PD5_86") (pintype "bidirectional"))
    )
    (net (code "81") (name "unconnected-(F4A-PD6-Pad87)") (class "Default")
      (node (ref "F4") (pin "87") (pinfunction "PD6_87") (pintype "bidirectional"))
    )
    (net (code "82") (name "unconnected-(F4A-PD7-Pad88)") (class "Default")
      (node (ref "F4") (pin "88") (pinfunction "PD7_88") (pintype "bidirectional"))
    )
    (net (code "83") (name "unconnected-(F4A-PD10-Pad57)") (class "Default")
      (node (ref "F4") (pin "57") (pinfunction "PD10_57") (pintype "bidirectional"))
    )
    (net (code "84") (name "unconnected-(F4A-PD11-Pad58)") (class "Default")
      (node (ref "F4") (pin "58") (pinfunction "PD11_58") (pintype "bidirectional"))
    )
    (net (code "85") (name "unconnected-(F4A-PE0-Pad97)") (class "Default")
      (node (ref "F4") (pin "97") (pinfunction "PE0_97") (pintype "bidirectional"))
    )
    (net (code "86") (name "unconnected-(F4A-PE1-Pad98)") (class "Default")
      (node (ref "F4") (pin "98") (pinfunction "PE1_98") (pintype "bidirectional"))
    )
    (net (code "87") (name "unconnected-(F4A-PE2-Pad1)") (class "Default")
      (node (ref "F4") (pin "1") (pinfunction "PE2_1") (pintype "bidirectional"))
    )
    (net (code "88") (name "unconnected-(F4A-PE3-Pad2)") (class "Default")
      (node (ref "F4") (pin "2") (pinfunction "PE3_2") (pintype "bidirectional"))
    )
    (net (code "89") (name "unconnected-(F4A-PE4-Pad3)") (class "Default")
      (node (ref "F4") (pin "3") (pinfunction "PE4_3") (pintype "bidirectional"))
    )
    (net (code "90") (name "unconnected-(F4A-PE5-Pad4)") (class "Default")
      (node (ref "F4") (pin "4") (pinfunction "PE5_4") (pintype "bidirectional"))
    )
    (net (code "91") (name "unconnected-(F4A-PE6-Pad5)") (class "Default")
      (node (ref "F4") (pin "5") (pinfunction "PE6_5") (pintype "bidirectional"))
    )
    (net (code "92") (name "unconnected-(F4A-PE7-Pad38)") (class "Default")
      (node (ref "F4") (pin "38") (pinfunction "PE7_38") (pintype "bidirectional"))
    )
    (net (code "93") (name "unconnected-(F4A-PE8-Pad39)") (class "Default")
      (node (ref "F4") (pin "39") (pinfunction "PE8_39") (pintype "bidirectional"))
    )
    (net (code "94") (name "unconnected-(F4A-PE9-Pad40)") (class "Default")
      (node (ref "F4") (pin "40") (pinfunction "PE9_40") (pintype "bidirectional"))
    )
    (net (code "95") (name "unconnected-(F4A-PE10-Pad41)") (class "Default")
      (node (ref "F4") (pin "41") (pinfunction "PE10_41") (pintype "bidirectional"))
    )
    (net (code "96") (name "unconnected-(F4A-PE11-Pad42)") (class "Default")
      (node (ref "F4") (pin "42") (pinfunction "PE11_42") (pintype "bidirectional"))
    )
    (net (code "97") (name "unconnected-(F4A-PE14-Pad45)") (class "Default")
      (node (ref "F4") (pin "45") (pinfunction "PE14_45") (pintype "bidirectional"))
    )
    (net (code "98") (name "unconnected-(F4A-PE15-Pad46)") (class "Default")
      (node (ref "F4") (pin "46") (pinfunction "PE15_46") (pintype "bidirectional"))
    )
    (net (code "99") (name "unconnected-(F4B-VBAT-Pad6)") (class "Default")
      (node (ref "F4") (pin "6") (pinfunction "VBAT_6") (pintype "power_in"))
    )
    (net (code "100") (name "unconnected-(RC-Pad6)") (class "Default")
      (node (ref "RC") (pin "6") (pinfunction "6_6") (pintype "passive+no_connect"))
    )
    (net (code "101") (name "unconnected-(RC-Pad7)") (class "Default")
      (node (ref "RC") (pin "7") (pinfunction "7_7") (pintype "passive+no_connect"))
    )
    (net (code "102") (name "unconnected-(RC-Pad8)") (class "Default")
      (node (ref "RC") (pin "8") (pinfunction "8_8") (pintype "passive+no_connect"))
    )
    (net (code "103") (name "unconnected-(RC-Pad10)") (class "Default")
      (node (ref "RC") (pin "10") (pinfunction "10_10") (pintype "passive+no_connect"))
    )
    (net (code "104") (name "unconnected-(RC-Pad11)") (class "Default")
      (node (ref "RC") (pin "11") (pinfunction "11_11") (pintype "passive+no_connect"))
    )
    (net (code "105") (name "unconnected-(RC-Pad12)") (class "Default")
      (node (ref "RC") (pin "12") (pinfunction "12_12") (pintype "passive+no_connect"))
    )
    (net (code "106") (name "unconnected-(RC-Pad13)") (class "Default")
      (node (ref "RC") (pin "13") (pinfunction "13_13") (pintype "passive+no_connect"))
    )
    (net (code "107") (name "unconnected-(RC-Pad14)") (class "Default")
      (node (ref "RC") (pin "14") (pinfunction "14_14") (pintype "passive+no_connect"))
    )
    (net (code "108") (name "unconnected-(RC-Pad15)") (class "Default")
      (node (ref "RC") (pin "15") (pinfunction "15_15") (pintype "passive+no_connect"))
    )
    (net (code "109") (name "unconnected-(RC-Pad16)") (class "Default")
      (node (ref "RC") (pin "16") (pinfunction "16_16") (pintype "passive+no_connect"))
    )
  )
)
